# mic.net
KiCad netlist of a schematic drawn in Altium Designer
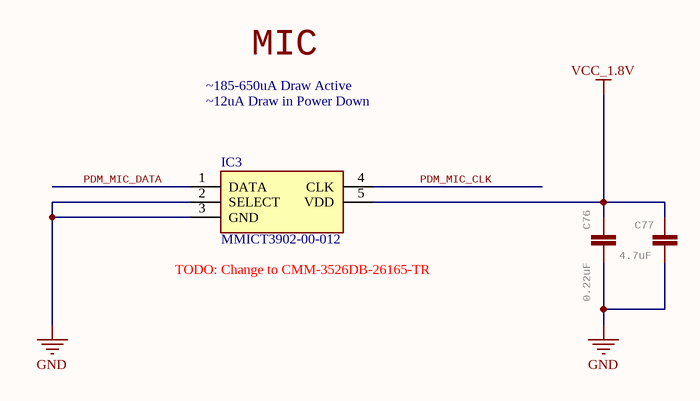
[diagram p0: mic.SchDoc]

(export (version "E")
  (design (tool "Eeschema 10.0.6"))
  (components
    (comp (ref "C76")
      (value "0.22uF")
      (footprint "C0201")
      (description "CAPACITOR, European symbol")
      (fields (field (name "MPN") "GRM033R60J224ME15D"))
      (libsource (lib "openmv-ae3") (part "C-EUC0201"))
    )
    (comp (ref "C77")
      (value "4.7uF")
      (footprint "0402-CAP")
      (description "CapacitorStandard 0603 ceramic capacitor, and 0.1\" leaded capacitor.")
      (fields (field (name "MPN") "JMK105BBJ475MV-F") (field (name "LIBRARYNAME") "sfe"))
      (libsource (lib "openmv-ae3") (part "CAP0402-CAP"))
    )
    (comp (ref "IC3")
      (value "MMICT3902-00-012")
      (footprint "SamacSys:MMICT390200012")
      (description "Integrated Circuit")
      (fields (field (name "MOUSER PART NUMBER") "410-MMICT3902-00-012"))
      (libsource (lib "*") (part "MMICT3902-00-012"))
    )
  )
  (nets
    (net (code "1") (name "/PDM_MIC_CLK") (class "Default")
      (node (ref "IC3") (pin "4") (pinfunction "CLK_4") (pintype "passive"))
    )
    (net (code "2") (name "/PDM_MIC_DATA") (class "Default")
      (node (ref "IC3") (pin "1") (pinfunction "DATA_1") (pintype "passive"))
    )
    (net (code "3") (name "GND") (class "Default")
      (node (ref "C76") (pin "2") (pinfunction "2_2") (pintype "passive"))
      (node (ref "C77") (pin "1") (pinfunction "1_1") (pintype "passive"))
      (node (ref "IC3") (pin "2") (pinfunction "SELECT_2") (pintype "passive"))
      (node (ref "IC3") (pin "3") (pinfunction "GND_3") (pintype "passive"))
    )
    (net (code "4") (name "VCC_1.8V") (class "Default")
      (node (ref "C76") (pin "1") (pinfunction "1_1") (pintype "passive"))
      (node (ref "C77") (pin "2") (pinfunction "2_2") (pintype "passive"))
      (node (ref "IC3") (pin "5") (pinfunction "VDD_5") (pintype "passive"))
    )
  )
)
